# nanoIO-v2_2.net
KiCad netlist of a schematic drawn in EAGLE
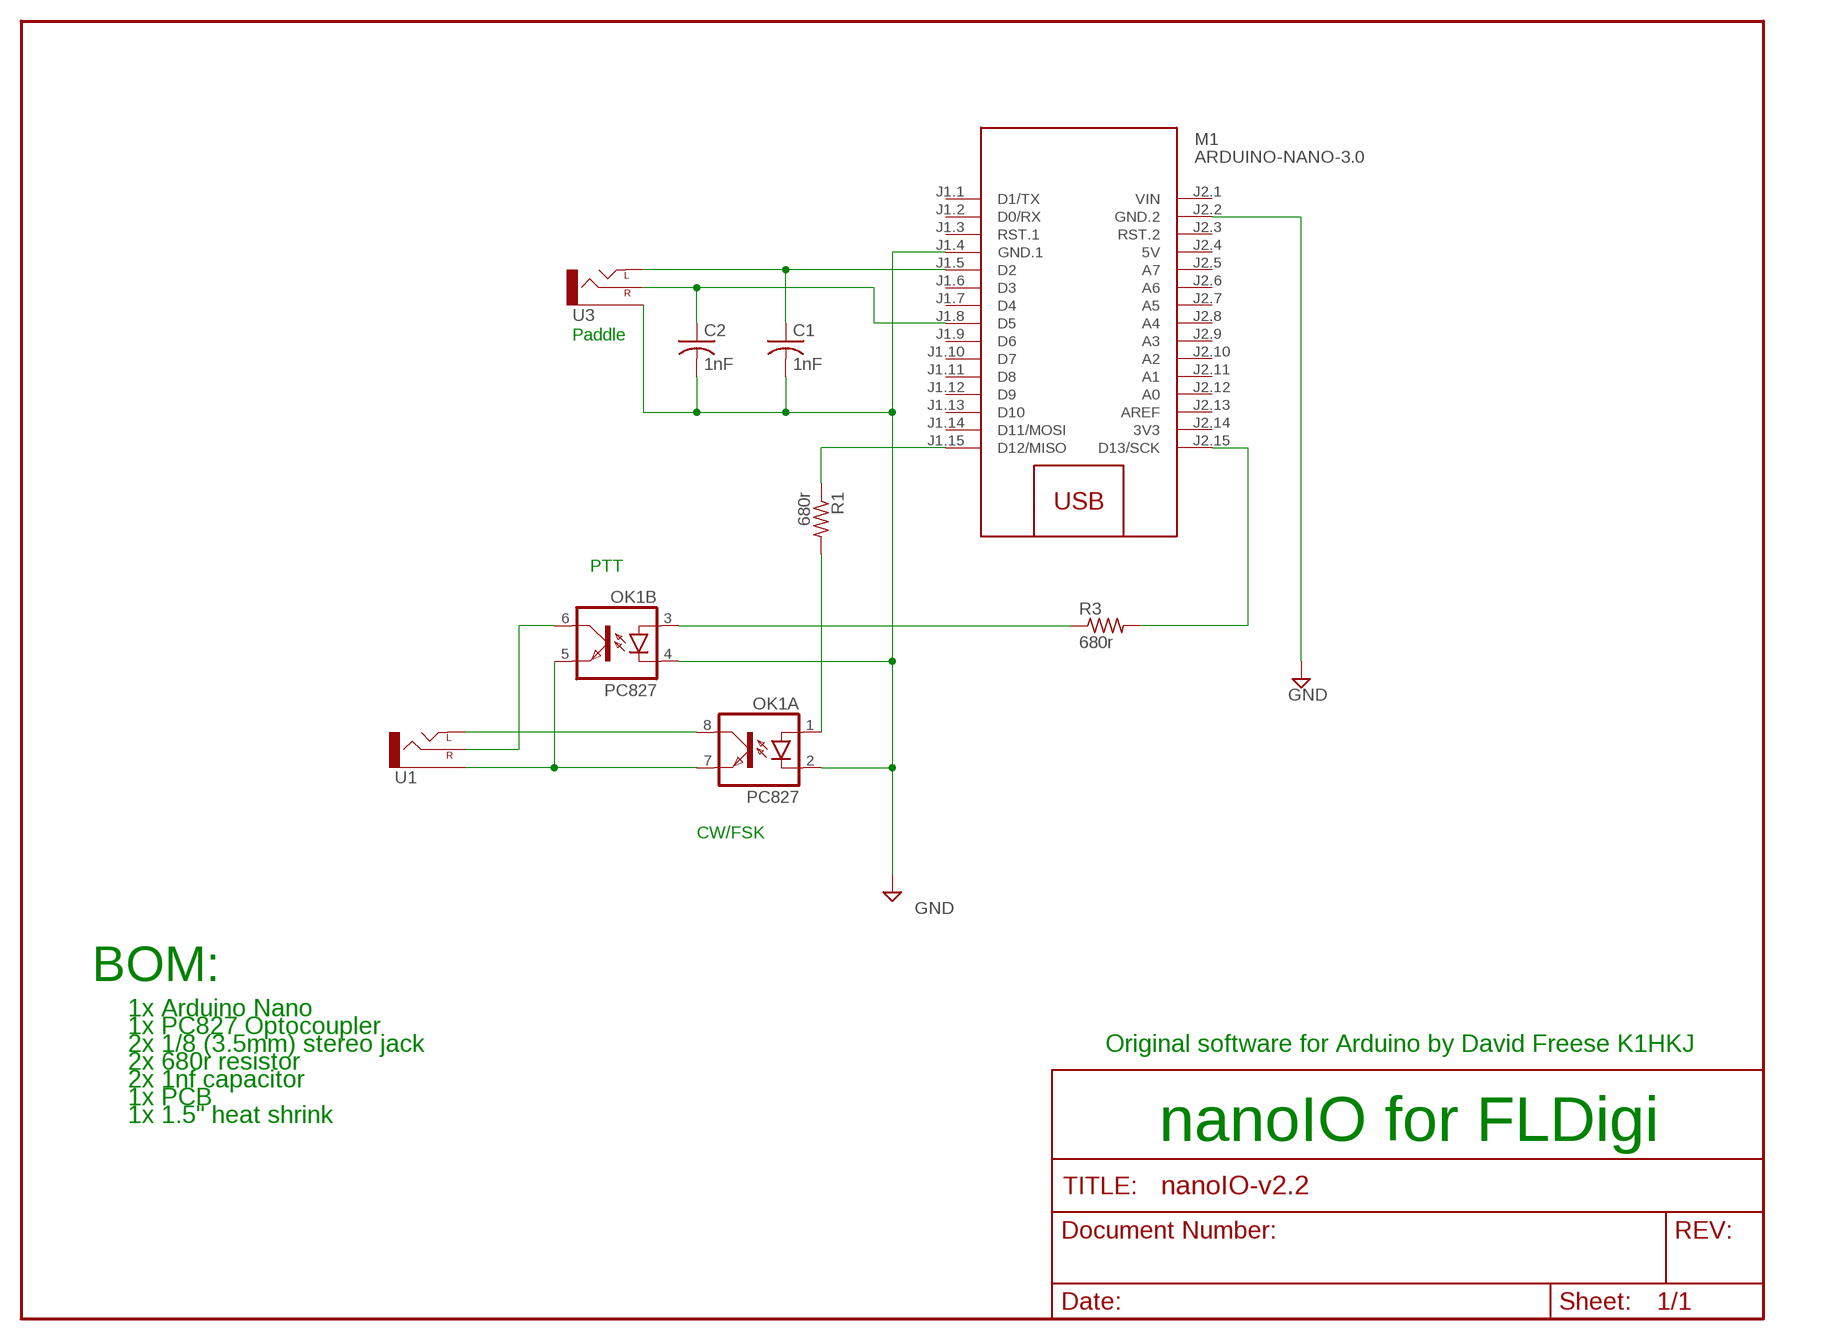
[diagram p0: schematic, sheet 1]

(export (version "E")
  (design (tool "Eeschema 10.0.6"))
  (components
    (comp (ref "C1")
      (value "1nF")
      (footprint "eagle-import:C025-025X050")
      (libsource (lib "eagle-import") (part "C-US025-025X050"))
    )
    (comp (ref "C2")
      (value "1nF")
      (footprint "eagle-import:C025-025X050")
      (libsource (lib "eagle-import") (part "C-US025-025X050"))
    )
    (comp (ref "M1")
      (value "ARDUINO-NANO-3.0")
      (footprint "eagle-import:ARDUINO-NANO-3.0")
      (libsource (lib "eagle-import") (part "ARDUINO-NANO-3.0"))
    )
    (comp (ref "OK1")
      (value "PC827")
      (footprint "eagle-import:DIL08")
      (libsource (lib "eagle-import") (part "PC827"))
    )
    (comp (ref "R1")
      (value "680r")
      (footprint "eagle-import:0204_7")
      (libsource (lib "eagle-import") (part "R-US_0204/7"))
    )
    (comp (ref "R3")
      (value "680r")
      (footprint "eagle-import:0204_7")
      (libsource (lib "eagle-import") (part "R-US_0204/7"))
    )
    (comp (ref "U1")
      (value "AUDIO-JACKPTH")
      (footprint "eagle-import:AUDIO-JACK")
      (libsource (lib "eagle-import") (part "AUDIO-JACKPTH"))
    )
    (comp (ref "U3")
      (value "AUDIO-JACKPTH")
      (footprint "eagle-import:AUDIO-JACK")
      (libsource (lib "eagle-import") (part "AUDIO-JACKPTH"))
    )
  )
  (nets
    (net (code "1") (name "/3V3") (class "Default")
      (node (ref "M1") (pin "J2.14") (pinfunction "3V3_J2.14") (pintype "power_in"))
    )
    (net (code "2") (name "/5V") (class "Default")
      (node (ref "M1") (pin "J2.4") (pinfunction "5V_J2.4") (pintype "power_in"))
    )
    (net (code "3") (name "/VIN") (class "Default")
      (node (ref "M1") (pin "J2.1") (pinfunction "VIN_J2.1") (pintype "power_in"))
    )
    (net (code "4") (name "GND") (class "Default")
      (node (ref "C1") (pin "2") (pinfunction "2_2") (pintype "passive"))
      (node (ref "C2") (pin "2") (pinfunction "2_2") (pintype "passive"))
      (node (ref "M1") (pin "J1.4") (pinfunction "GND.1_J1.4") (pintype "power_in"))
      (node (ref "M1") (pin "J2.2") (pinfunction "GND.2_J2.2") (pintype "power_in"))
      (node (ref "OK1") (pin "2") (pinfunction "C_2") (pintype "passive"))
      (node (ref "OK1") (pin "4") (pinfunction "C_4") (pintype "passive"))
      (node (ref "U3") (pin "SLEEVE") (pinfunction "SLEEVE_SLEEVE") (pintype "bidirectional"))
    )
    (net (code "5") (name "Net-(M1-D2)") (class "Default")
      (node (ref "C1") (pin "1") (pinfunction "1_1") (pintype "passive"))
      (node (ref "M1") (pin "J1.5") (pinfunction "D2_J1.5") (pintype "bidirectional"))
      (node (ref "U3") (pin "TIP") (pinfunction "LEFT_TIP") (pintype "bidirectional"))
    )
    (net (code "6") (name "Net-(M1-D5)") (class "Default")
      (node (ref "C2") (pin "1") (pinfunction "1_1") (pintype "passive"))
      (node (ref "M1") (pin "J1.8") (pinfunction "D5_J1.8") (pintype "bidirectional"))
      (node (ref "U3") (pin "RING") (pinfunction "RIGHT_RING") (pintype "bidirectional"))
    )
    (net (code "7") (name "Net-(M1-D12{slash}MISO)") (class "Default")
      (node (ref "M1") (pin "J1.15") (pinfunction "D12/MISO_J1.15") (pintype "bidirectional"))
      (node (ref "R1") (pin "1") (pinfunction "1_1") (pintype "passive"))
    )
    (net (code "8") (name "Net-(M1-D13{slash}SCK)") (class "Default")
      (node (ref "M1") (pin "J2.15") (pinfunction "D13/SCK_J2.15") (pintype "bidirectional"))
      (node (ref "R3") (pin "2") (pinfunction "2_2") (pintype "passive"))
    )
    (net (code "9") (name "Net-(OK1A-A)") (class "Default")
      (node (ref "OK1") (pin "1") (pinfunction "A_1") (pintype "passive"))
      (node (ref "R1") (pin "2") (pinfunction "2_2") (pintype "passive"))
    )
    (net (code "10") (name "Net-(OK1A-COL)") (class "Default")
      (node (ref "OK1") (pin "8") (pinfunction "COL_8") (pintype "passive"))
      (node (ref "U1") (pin "TIP") (pinfunction "LEFT_TIP") (pintype "bidirectional"))
    )
    (net (code "11") (name "Net-(OK1A-EMIT)") (class "Default")
      (node (ref "OK1") (pin "5") (pinfunction "EMIT_5") (pintype "passive"))
      (node (ref "OK1") (pin "7") (pinfunction "EMIT_7") (pintype "passive"))
      (node (ref "U1") (pin "SLEEVE") (pinfunction "SLEEVE_SLEEVE") (pintype "bidirectional"))
    )
    (net (code "12") (name "Net-(OK1B-A)") (class "Default")
      (node (ref "OK1") (pin "3") (pinfunction "A_3") (pintype "passive"))
      (node (ref "R3") (pin "1") (pinfunction "1_1") (pintype "passive"))
    )
    (net (code "13") (name "Net-(OK1B-COL)") (class "Default")
      (node (ref "OK1") (pin "6") (pinfunction "COL_6") (pintype "passive"))
      (node (ref "U1") (pin "RING") (pinfunction "RIGHT_RING") (pintype "bidirectional"))
    )
    (net (code "14") (name "unconnected-(M1-A0-PadJ2.12)") (class "Default")
      (node (ref "M1") (pin "J2.12") (pinfunction "A0_J2.12") (pintype "bidirectional"))
    )
    (net (code "15") (name "unconnected-(M1-A1-PadJ2.11)") (class "Default")
      (node (ref "M1") (pin "J2.11") (pinfunction "A1_J2.11") (pintype "bidirectional"))
    )
    (net (code "16") (name "unconnected-(M1-A2-PadJ2.10)") (class "Default")
      (node (ref "M1") (pin "J2.10") (pinfunction "A2_J2.10") (pintype "bidirectional"))
    )
    (net (code "17") (name "unconnected-(M1-A3-PadJ2.9)") (class "Default")
      (node (ref "M1") (pin "J2.9") (pinfunction "A3_J2.9") (pintype "bidirectional"))
    )
    (net (code "18") (name "unconnected-(M1-A4-PadJ2.8)") (class "Default")
      (node (ref "M1") (pin "J2.8") (pinfunction "A4_J2.8") (pintype "bidirectional"))
    )
    (net (code "19") (name "unconnected-(M1-A5-PadJ2.7)") (class "Default")
      (node (ref "M1") (pin "J2.7") (pinfunction "A5_J2.7") (pintype "bidirectional"))
    )
    (net (code "20") (name "unconnected-(M1-A6-PadJ2.6)") (class "Default")
      (node (ref "M1") (pin "J2.6") (pinfunction "A6_J2.6") (pintype "bidirectional"))
    )
    (net (code "21") (name "unconnected-(M1-A7-PadJ2.5)") (class "Default")
      (node (ref "M1") (pin "J2.5") (pinfunction "A7_J2.5") (pintype "bidirectional"))
    )
    (net (code "22") (name "unconnected-(M1-AREF-PadJ2.13)") (class "Default")
      (node (ref "M1") (pin "J2.13") (pinfunction "AREF_J2.13") (pintype "bidirectional"))
    )
    (net (code "23") (name "unconnected-(M1-D0{slash}RX-PadJ1.2)") (class "Default")
      (node (ref "M1") (pin "J1.2") (pinfunction "D0/RX_J1.2") (pintype "bidirectional"))
    )
    (net (code "24") (name "unconnected-(M1-D1{slash}TX-PadJ1.1)") (class "Default")
      (node (ref "M1") (pin "J1.1") (pinfunction "D1/TX_J1.1") (pintype "bidirectional"))
    )
    (net (code "25") (name "unconnected-(M1-D3-PadJ1.6)") (class "Default")
      (node (ref "M1") (pin "J1.6") (pinfunction "D3_J1.6") (pintype "bidirectional"))
    )
    (net (code "26") (name "unconnected-(M1-D4-PadJ1.7)") (class "Default")
      (node (ref "M1") (pin "J1.7") (pinfunction "D4_J1.7") (pintype "bidirectional"))
    )
    (net (code "27") (name "unconnected-(M1-D6-PadJ1.9)") (class "Default")
      (node (ref "M1") (pin "J1.9") (pinfunction "D6_J1.9") (pintype "bidirectional"))
    )
    (net (code "28") (name "unconnected-(M1-D7-PadJ1.10)") (class "Default")
      (node (ref "M1") (pin "J1.10") (pinfunction "D7_J1.10") (pintype "bidirectional"))
    )
    (net (code "29") (name "unconnected-(M1-D8-PadJ1.11)") (class "Default")
      (node (ref "M1") (pin "J1.11") (pinfunction "D8_J1.11") (pintype "bidirectional"))
    )
    (net (code "30") (name "unconnected-(M1-D9-PadJ1.12)") (class "Default")
      (node (ref "M1") (pin "J1.12") (pinfunction "D9_J1.12") (pintype "bidirectional"))
    )
    (net (code "31") (name "unconnected-(M1-D10-PadJ1.13)") (class "Default")
      (node (ref "M1") (pin "J1.13") (pinfunction "D10_J1.13") (pintype "bidirectional"))
    )
    (net (code "32") (name "unconnected-(M1-D11{slash}MOSI-PadJ1.14)") (class "Default")
      (node (ref "M1") (pin "J1.14") (pinfunction "D11/MOSI_J1.14") (pintype "bidirectional"))
    )
    (net (code "33") (name "unconnected-(M1-RST.1-PadJ1.3)") (class "Default")
      (node (ref "M1") (pin "J1.3") (pinfunction "RST.1_J1.3") (pintype "bidirectional"))
    )
    (net (code "34") (name "unconnected-(M1-RST.2-PadJ2.3)") (class "Default")
      (node (ref "M1") (pin "J2.3") (pinfunction "RST.2_J2.3") (pintype "bidirectional"))
    )
  )
)
